# TELESPOR_ADAPTER.net
KiCad netlist of a schematic drawn in Altium Designer
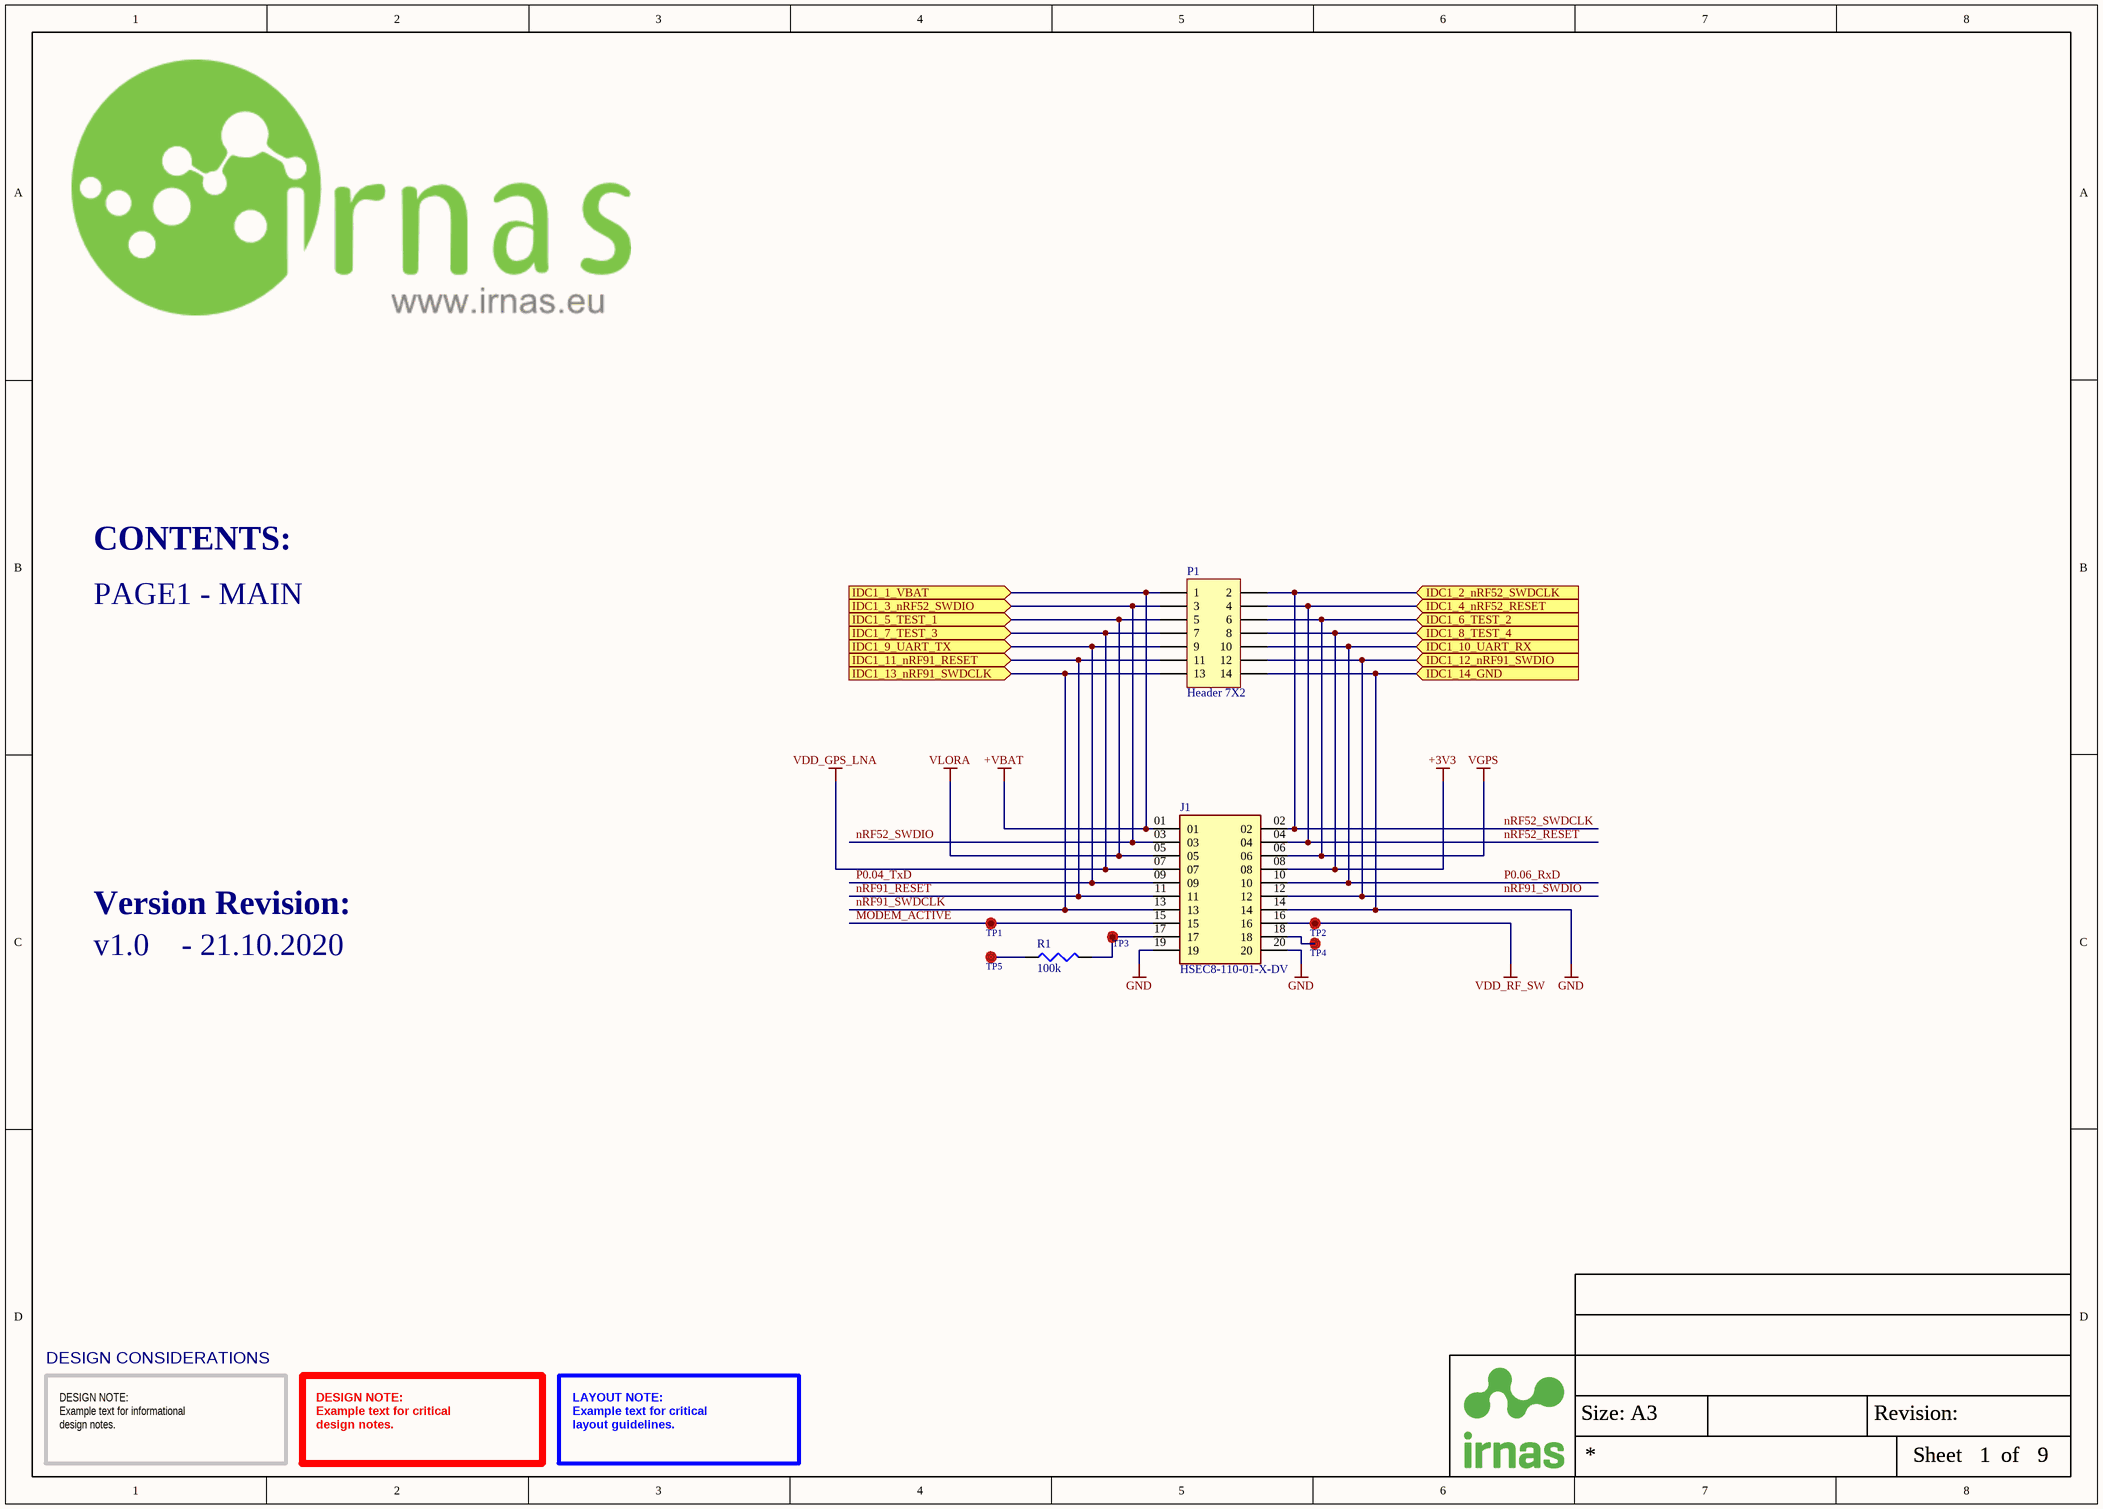
[diagram p0: TELESPOR_ADAPTER.SchDoc]

(export (version "E")
  (design (tool "Eeschema 10.0.6"))
  (components
    (comp (ref "J1")
      (value "HSEC8-110-01-X-DV")
      (footprint "Connectors:SAMTEC_HSEC8-110-01-X-DV")
      (description "20 Position Female Connector Non Specified - Dual Edge Gold 0.031 (0.80mm) Black")
      (fields (field (name "MF") "Samtec") (field (name "MP") "HSEC8-110-01-L-DV"))
      (libsource (lib "Connectors") (part "HSEC8-110-01-X-DV"))
    )
    (comp (ref "P1")
      (value "Header 7X2")
      (footprint "HDR2X7")
      (description "Header, 7-Pin, Dual row")
      (fields (field (name "PUBLISHER") "Altium Limited"))
      (libsource (lib "Miscellaneous Connectors") (part "Header 7X2"))
    )
    (comp (ref "R1")
      (value "100k")
      (footprint "RES0402")
      (description "MULTICOMP   MCWR04X1003FTL   RES, THICK FILM, 100KOHM, 1%, 0.0625W")
      (fields
        (field (name "MANUFACTURER") "Multicomp")
        (field (name "MANUFACTURER PART NUMBER") "MCWR04X1003FTL")
      )
      (libsource (lib "Passive") (part "R - 100k/0402"))
    )
    (comp (ref "TP1")
      (value "TestPoint")
      (footprint "Passive:TestPoint:1.2x1.2mm")
      (description "TEST POINT ROUND SMD")
      (libsource (lib "Passive") (part "TestPoint"))
    )
    (comp (ref "TP2")
      (value "TestPoint")
      (footprint "Passive:TestPoint:1.2x1.2mm")
      (description "TEST POINT ROUND SMD")
      (libsource (lib "Passive") (part "TestPoint"))
    )
    (comp (ref "TP3")
      (value "TestPoint")
      (footprint "Passive:TestPoint:1.2x1.2mm")
      (description "TEST POINT ROUND SMD")
      (libsource (lib "Passive") (part "TestPoint"))
    )
    (comp (ref "TP4")
      (value "TestPoint")
      (footprint "Passive:TestPoint:1.2x1.2mm")
      (description "TEST POINT ROUND SMD")
      (libsource (lib "Passive") (part "TestPoint"))
    )
    (comp (ref "TP5")
      (value "TestPoint")
      (footprint "Passive:TestPoint:1.2x1.2mm")
      (description "TEST POINT ROUND SMD")
      (libsource (lib "Passive") (part "TestPoint"))
    )
  )
  (nets
    (net (code "1") (name "+3V3") (class "Default")
      (node (ref "J1") (pin "08") (pinfunction "08_08") (pintype "passive"))
      (node (ref "P1") (pin "8") (pinfunction "8_8") (pintype "passive"))
    )
    (net (code "2") (name "+VBAT") (class "Default")
      (node (ref "J1") (pin "01") (pinfunction "01_01") (pintype "passive"))
      (node (ref "P1") (pin "1") (pinfunction "1_1") (pintype "passive"))
    )
    (net (code "3") (name "/MODEM_ACTIVE") (class "Default")
      (node (ref "J1") (pin "15") (pinfunction "15_15") (pintype "passive"))
      (node (ref "TP1") (pin "0") (pinfunction "0_0") (pintype "passive"))
    )
    (net (code "4") (name "/P0.04_TxD") (class "Default")
      (node (ref "J1") (pin "09") (pinfunction "09_09") (pintype "passive"))
      (node (ref "P1") (pin "9") (pinfunction "9_9") (pintype "passive"))
    )
    (net (code "5") (name "/P0.06_RxD") (class "Default")
      (node (ref "J1") (pin "10") (pinfunction "10_10") (pintype "passive"))
      (node (ref "P1") (pin "10") (pinfunction "10_10") (pintype "passive"))
    )
    (net (code "6") (name "/nRF52_RESET") (class "Default")
      (node (ref "J1") (pin "04") (pinfunction "04_04") (pintype "passive"))
      (node (ref "P1") (pin "4") (pinfunction "4_4") (pintype "passive"))
    )
    (net (code "7") (name "/nRF52_SWDCLK") (class "Default")
      (node (ref "J1") (pin "02") (pinfunction "02_02") (pintype "passive"))
      (node (ref "P1") (pin "2") (pinfunction "2_2") (pintype "passive"))
    )
    (net (code "8") (name "/nRF52_SWDIO") (class "Default")
      (node (ref "J1") (pin "03") (pinfunction "03_03") (pintype "passive"))
      (node (ref "P1") (pin "3") (pinfunction "3_3") (pintype "passive"))
    )
    (net (code "9") (name "/nRF91_RESET") (class "Default")
      (node (ref "J1") (pin "11") (pinfunction "11_11") (pintype "passive"))
      (node (ref "P1") (pin "11") (pinfunction "11_11") (pintype "passive"))
    )
    (net (code "10") (name "/nRF91_SWDCLK") (class "Default")
      (node (ref "J1") (pin "13") (pinfunction "13_13") (pintype "passive"))
      (node (ref "P1") (pin "13") (pinfunction "13_13") (pintype "passive"))
    )
    (net (code "11") (name "/nRF91_SWDIO") (class "Default")
      (node (ref "J1") (pin "12") (pinfunction "12_12") (pintype "passive"))
      (node (ref "P1") (pin "12") (pinfunction "12_12") (pintype "passive"))
    )
    (net (code "12") (name "GND") (class "Default")
      (node (ref "J1") (pin "14") (pinfunction "14_14") (pintype "passive"))
      (node (ref "J1") (pin "19") (pinfunction "19_19") (pintype "passive"))
      (node (ref "J1") (pin "20") (pinfunction "20_20") (pintype "passive"))
      (node (ref "P1") (pin "14") (pinfunction "14_14") (pintype "passive"))
    )
    (net (code "13") (name "Net-(J1-Pad17)") (class "Default")
      (node (ref "J1") (pin "17") (pinfunction "17_17") (pintype "passive"))
      (node (ref "R1") (pin "2") (pinfunction "2_2") (pintype "passive"))
      (node (ref "TP3") (pin "0") (pinfunction "0_0") (pintype "passive"))
    )
    (net (code "14") (name "Net-(J1-Pad18)") (class "Default")
      (node (ref "J1") (pin "18") (pinfunction "18_18") (pintype "passive"))
      (node (ref "TP4") (pin "0") (pinfunction "0_0") (pintype "passive"))
    )
    (net (code "15") (name "Net-(R1-Pad1)") (class "Default")
      (node (ref "R1") (pin "1") (pinfunction "1_1") (pintype "passive"))
      (node (ref "TP5") (pin "0") (pinfunction "0_0") (pintype "passive"))
    )
    (net (code "16") (name "VDD_GPS_LNA") (class "Default")
      (node (ref "J1") (pin "07") (pinfunction "07_07") (pintype "passive"))
      (node (ref "P1") (pin "7") (pinfunction "7_7") (pintype "passive"))
    )
    (net (code "17") (name "VDD_RF_SW") (class "Default")
      (node (ref "J1") (pin "16") (pinfunction "16_16") (pintype "passive"))
      (node (ref "TP2") (pin "0") (pinfunction "0_0") (pintype "passive"))
    )
    (net (code "18") (name "VGPS") (class "Default")
      (node (ref "J1") (pin "06") (pinfunction "06_06") (pintype "passive"))
      (node (ref "P1") (pin "6") (pinfunction "6_6") (pintype "passive"))
    )
    (net (code "19") (name "VLORA") (class "Default")
      (node (ref "J1") (pin "05") (pinfunction "05_05") (pintype "passive"))
      (node (ref "P1") (pin "5") (pinfunction "5_5") (pintype "passive"))
    )
  )
)
